# Main.net
KiCad netlist of a schematic drawn in Altium Designer
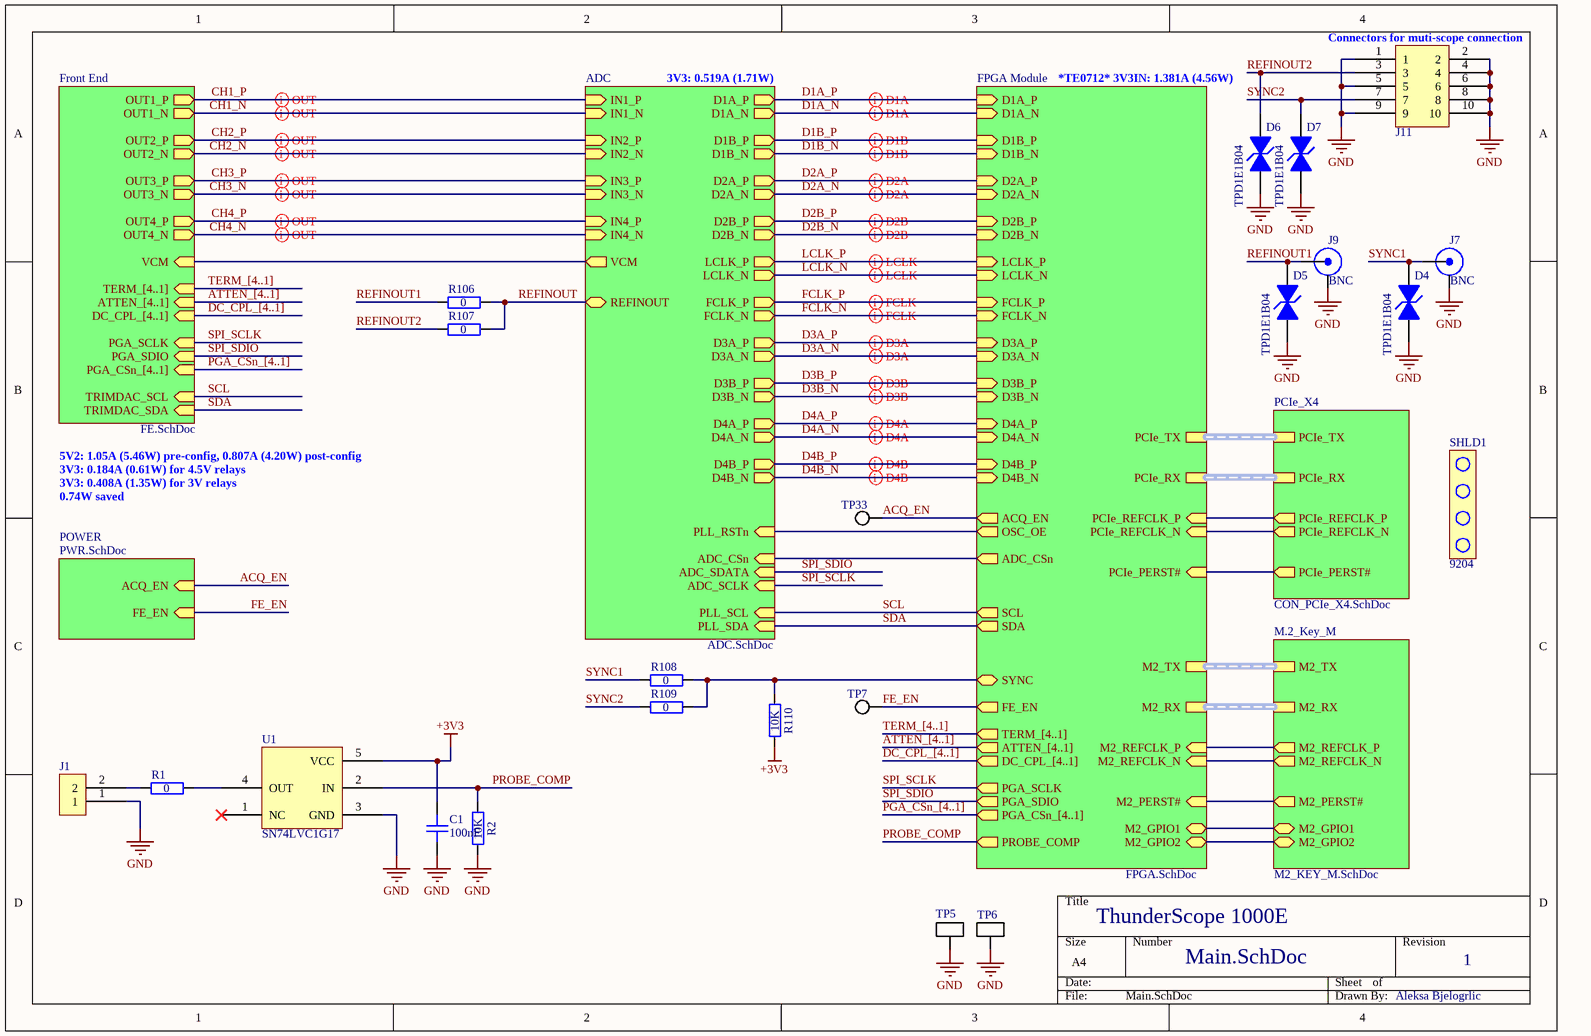
[diagram p0: Main.SchDoc]

(export (version "E")
  (design (tool "Eeschema 10.0.6"))
  (components
    (comp (ref "C1")
      (value "100nF")
      (footprint "GEN_C_0402")
      (libsource (lib "DSO") (part "CAP 100nF 16V X7R 0402"))
    )
    (comp (ref "D4")
      (value "TPD1E1B04")
      (footprint "TI_X1SON_DPY0002A")
      (libsource (lib "DSO") (part "TVS TPD1E1B04"))
    )
    (comp (ref "D5")
      (value "TPD1E1B04")
      (footprint "TI_X1SON_DPY0002A")
      (libsource (lib "DSO") (part "TVS TPD1E1B04"))
    )
    (comp (ref "D6")
      (value "TPD1E1B04")
      (footprint "TI_X1SON_DPY0002A")
      (libsource (lib "DSO") (part "TVS TPD1E1B04"))
    )
    (comp (ref "D7")
      (value "TPD1E1B04")
      (footprint "TI_X1SON_DPY0002A")
      (libsource (lib "DSO") (part "TVS TPD1E1B04"))
    )
    (comp (ref "J1")
      (value "TSW-101-08-F-D-RA")
      (footprint "GEN_2.54mm_1x2_Pin_TH_RA")
      (libsource (lib "DSO") (part "CONN 2.54mm 2 Pin TH RA"))
    )
    (comp (ref "J7") (value "BNC") (footprint "MOL_0731000105") (libsource (lib "DSO") (part "BNC JACK R/A")))
    (comp (ref "J9") (value "BNC") (footprint "MOL_0731000105") (libsource (lib "DSO") (part "BNC JACK R/A")))
    (comp (ref "J11")
      (value "1.27mm 6 Pin TH")
      (footprint "GEN_1.27mm_2x5_Pin_TH_RA")
      (libsource (lib "DSO") (part "CONN 1.27mm 2x5 Pin TH RA"))
    )
    (comp (ref "R1")
      (value "0")
      (footprint "GEN_R_0402")
      (libsource (lib "DSO") (part "RES 0 OHM 1/16W 0402"))
    )
    (comp (ref "R2")
      (value "10K")
      (footprint "GEN_R_0402")
      (fields (field (name "TOLERANCE") "1%"))
      (libsource (lib "DSO") (part "RES 10K OHM 1% 1/10W 0402"))
    )
    (comp (ref "R106")
      (value "0")
      (footprint "GEN_R_0402")
      (libsource (lib "DSO") (part "RES 0 OHM 1/16W 0402"))
    )
    (comp (ref "R107")
      (value "0")
      (footprint "GEN_R_0402")
      (libsource (lib "DSO") (part "RES 0 OHM 1/16W 0402"))
    )
    (comp (ref "R108")
      (value "0")
      (footprint "GEN_R_0402")
      (libsource (lib "DSO") (part "RES 0 OHM 1/16W 0402"))
    )
    (comp (ref "R109")
      (value "0")
      (footprint "GEN_R_0402")
      (libsource (lib "DSO") (part "RES 0 OHM 1/16W 0402"))
    )
    (comp (ref "R110")
      (value "10K")
      (footprint "GEN_R_0402")
      (fields (field (name "TOLERANCE") "1%"))
      (libsource (lib "DSO") (part "RES 10K OHM 1% 1/10W 0402"))
    )
    (comp (ref "SHLD1") (value "9204") (libsource (lib "DSO") (part "PCIe IO Shield")))
    (comp (ref "TP5") (value "5019") (footprint "KEY_5019") (libsource (lib "DSO") (part "TP KEYSTONE 5019")))
    (comp (ref "TP6") (value "5019") (footprint "KEY_5019") (libsource (lib "DSO") (part "TP KEYSTONE 5019")))
    (comp (ref "TP7") (value "PCB") (footprint "GEN_TP_PCB") (libsource (lib "DSO") (part "TP PCB 1mm")))
    (comp (ref "TP33") (value "PCB") (footprint "GEN_TP_PCB") (libsource (lib "DSO") (part "TP PCB 1mm")))
    (comp (ref "U1")
      (value "SN74LVC1G17")
      (footprint "GEN_SC-70-5")
      (libsource (lib "DSO") (part "IC BUFFER SN74LVC1G17"))
    )
  )
  (nets
    (net (code "17") (name "+3V3") (class "Default")
      (node (ref "C1") (pin "1") (pinfunction "1_1") (pintype "passive"))
      (node (ref "R110") (pin "1") (pinfunction "1_1") (pintype "passive"))
      (node (ref "U1") (pin "5") (pinfunction "VCC_5") (pintype "passive"))
    )
    (net (code "18") (name "/ACQ_EN") (class "Default")
      (node (ref "TP33") (pin "1") (pinfunction "1_1") (pintype "passive"))
    )
    (net (code "48") (name "/FE_EN") (class "Default")
      (node (ref "TP7") (pin "1") (pinfunction "1_1") (pintype "passive"))
    )
    (net (code "65") (name "/PROBE_COMP") (class "Default")
      (node (ref "R2") (pin "2") (pinfunction "2_2") (pintype "passive"))
      (node (ref "U1") (pin "2") (pinfunction "IN_2") (pintype "passive"))
    )
    (net (code "66") (name "/REFINOUT") (class "Default")
      (node (ref "R106") (pin "2") (pinfunction "2_2") (pintype "passive"))
      (node (ref "R107") (pin "2") (pinfunction "2_2") (pintype "passive"))
    )
    (net (code "67") (name "/REFINOUT1") (class "Default")
      (node (ref "D5") (pin "1") (pinfunction "K_1") (pintype "passive"))
      (node (ref "J9") (pin "1") (pinfunction "Signal_1") (pintype "passive"))
      (node (ref "R106") (pin "1") (pinfunction "1_1") (pintype "passive"))
    )
    (net (code "68") (name "/REFINOUT2") (class "Default")
      (node (ref "D6") (pin "1") (pinfunction "K_1") (pintype "passive"))
      (node (ref "J11") (pin "3") (pinfunction "3_3") (pintype "passive"))
      (node (ref "R107") (pin "1") (pinfunction "1_1") (pintype "passive"))
    )
    (net (code "73") (name "/SYNC") (class "Default")
      (node (ref "R108") (pin "2") (pinfunction "2_2") (pintype "passive"))
      (node (ref "R109") (pin "2") (pinfunction "2_2") (pintype "passive"))
      (node (ref "R110") (pin "2") (pinfunction "2_2") (pintype "passive"))
    )
    (net (code "74") (name "/SYNC1") (class "Default")
      (node (ref "D4") (pin "1") (pinfunction "K_1") (pintype "passive"))
      (node (ref "J7") (pin "1") (pinfunction "Signal_1") (pintype "passive"))
      (node (ref "R108") (pin "1") (pinfunction "1_1") (pintype "passive"))
    )
    (net (code "75") (name "/SYNC2") (class "Default")
      (node (ref "D7") (pin "1") (pinfunction "K_1") (pintype "passive"))
      (node (ref "J11") (pin "7") (pinfunction "7_7") (pintype "passive"))
      (node (ref "R109") (pin "1") (pinfunction "1_1") (pintype "passive"))
    )
    (net (code "78") (name "GND") (class "Default")
      (node (ref "C1") (pin "2") (pinfunction "2_2") (pintype "passive"))
      (node (ref "D4") (pin "2") (pinfunction "A_2") (pintype "passive"))
      (node (ref "D5") (pin "2") (pinfunction "A_2") (pintype "passive"))
      (node (ref "D6") (pin "2") (pinfunction "A_2") (pintype "passive"))
      (node (ref "D7") (pin "2") (pinfunction "A_2") (pintype "passive"))
      (node (ref "J1") (pin "1") (pinfunction "1_1") (pintype "passive"))
      (node (ref "J11") (pin "1") (pinfunction "1_1") (pintype "passive"))
      (node (ref "J11") (pin "10") (pinfunction "10_10") (pintype "passive"))
      (node (ref "J11") (pin "2") (pinfunction "2_2") (pintype "passive"))
      (node (ref "J11") (pin "4") (pinfunction "4_4") (pintype "passive"))
      (node (ref "J11") (pin "5") (pinfunction "5_5") (pintype "passive"))
      (node (ref "J11") (pin "6") (pinfunction "6_6") (pintype "passive"))
      (node (ref "J11") (pin "8") (pinfunction "8_8") (pintype "passive"))
      (node (ref "J11") (pin "9") (pinfunction "9_9") (pintype "passive"))
      (node (ref "J7") (pin "2") (pinfunction "SHIELD_2") (pintype "passive"))
      (node (ref "J9") (pin "2") (pinfunction "SHIELD_2") (pintype "passive"))
      (node (ref "R2") (pin "1") (pinfunction "1_1") (pintype "passive"))
      (node (ref "TP5") (pin "1") (pinfunction "1_1") (pintype "passive"))
      (node (ref "TP6") (pin "1") (pinfunction "1_1") (pintype "passive"))
      (node (ref "U1") (pin "3") (pinfunction "GND_3") (pintype "passive"))
    )
    (net (code "79") (name "Net-(J1-Pad2)") (class "Default")
      (node (ref "J1") (pin "2") (pinfunction "2_2") (pintype "passive"))
      (node (ref "R1") (pin "1") (pinfunction "1_1") (pintype "passive"))
    )
    (net (code "80") (name "Net-(U1-OUT)") (class "Default")
      (node (ref "R1") (pin "2") (pinfunction "2_2") (pintype "passive"))
      (node (ref "U1") (pin "4") (pinfunction "OUT_4") (pintype "passive"))
    )
    (net (code "81") (name "unconnected-(U1-NC-Pad1)") (class "Default")
      (node (ref "U1") (pin "1") (pinfunction "NC_1") (pintype "passive+no_connect"))
    )
  )
)
